# fob.net
KiCad netlist of a schematic drawn in EAGLE
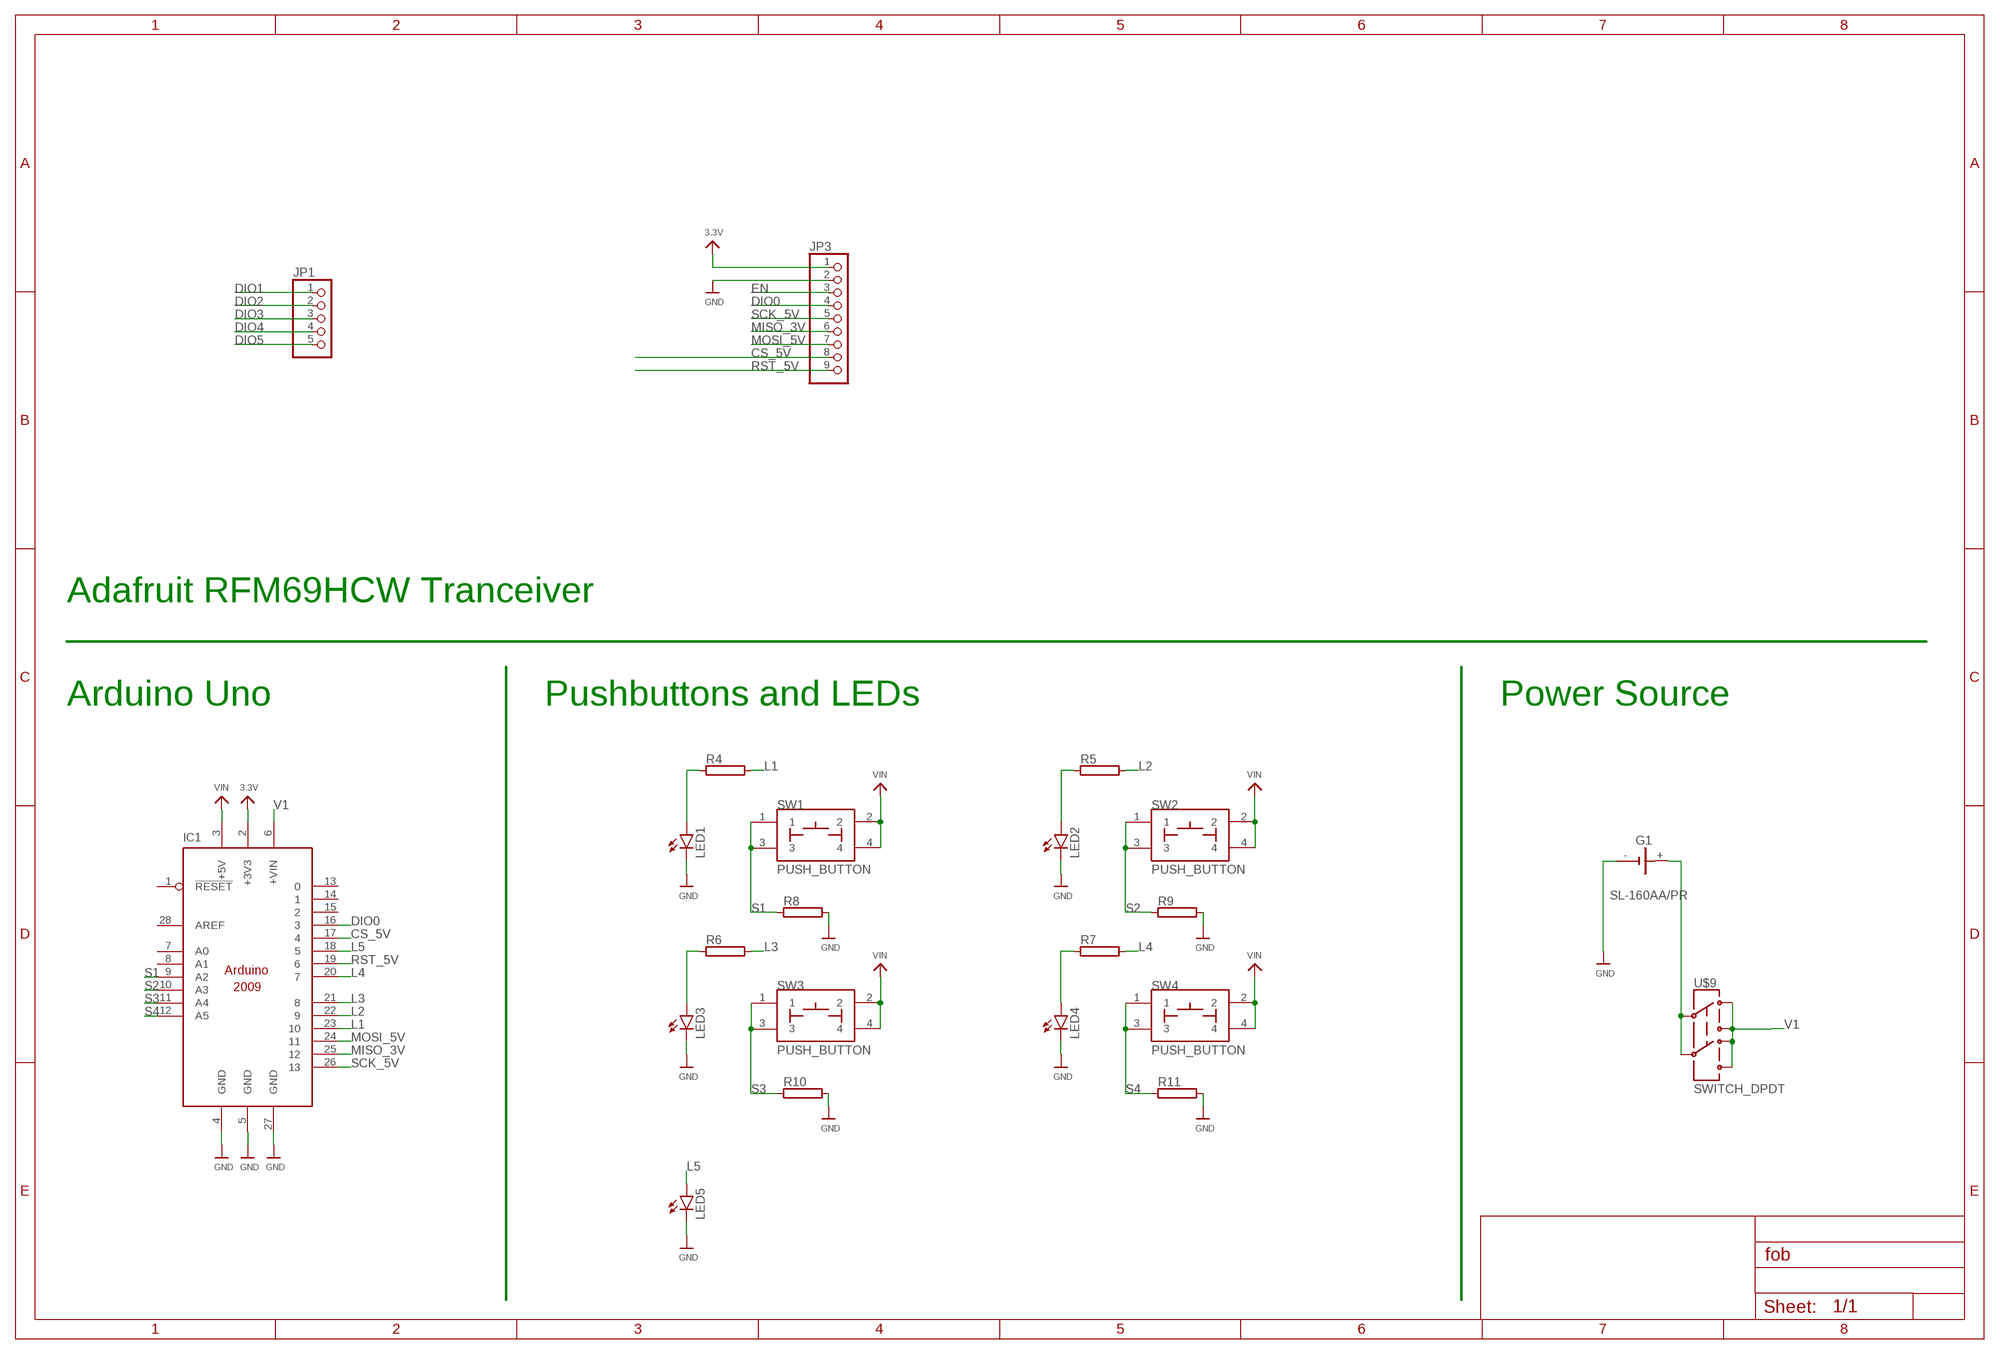
[diagram p0: schematic, sheet 1]

(export (version "E")
  (design (tool "Eeschema 10.0.6"))
  (components
    (comp (ref "G1")
      (value "SL-160AA/PR")
      (footprint "eagle-import:SL-160AA_PR")
      (libsource (lib "eagle-import") (part "SL-160AA/PR"))
    )
    (comp (ref "IC1")
      (value "ARDUINO2009_10")
      (footprint "eagle-import:ARDUINO2009")
      (libsource (lib "eagle-import") (part "ARDUINO2009_10"))
    )
    (comp (ref "JP1")
      (value "HEADER-1X570MIL")
      (footprint "eagle-import:1X05_ROUND_70")
      (libsource (lib "eagle-import") (part "HEADER-1X570MIL"))
    )
    (comp (ref "JP3")
      (value "HEADER-1X970MIL")
      (footprint "eagle-import:1X09_ROUND_70")
      (libsource (lib "eagle-import") (part "HEADER-1X970MIL"))
    )
    (comp (ref "LED1")
      (value "LED5MM")
      (footprint "eagle-import:LED5MM")
      (libsource (lib "eagle-import") (part "LED5MM"))
    )
    (comp (ref "LED2")
      (value "LED5MM")
      (footprint "eagle-import:LED5MM")
      (libsource (lib "eagle-import") (part "LED5MM"))
    )
    (comp (ref "LED3")
      (value "LED5MM")
      (footprint "eagle-import:LED5MM")
      (libsource (lib "eagle-import") (part "LED5MM"))
    )
    (comp (ref "LED4")
      (value "LED5MM")
      (footprint "eagle-import:LED5MM")
      (libsource (lib "eagle-import") (part "LED5MM"))
    )
    (comp (ref "LED5")
      (value "LED5MM")
      (footprint "eagle-import:LED5MM")
      (libsource (lib "eagle-import") (part "LED5MM"))
    )
    (comp (ref "R4")
      (value "RAC01")
      (footprint "eagle-import:AC01")
      (libsource (lib "eagle-import") (part "RAC01"))
    )
    (comp (ref "R5")
      (value "RAC01")
      (footprint "eagle-import:AC01")
      (libsource (lib "eagle-import") (part "RAC01"))
    )
    (comp (ref "R6")
      (value "RAC01")
      (footprint "eagle-import:AC01")
      (libsource (lib "eagle-import") (part "RAC01"))
    )
    (comp (ref "R7")
      (value "RAC01")
      (footprint "eagle-import:AC01")
      (libsource (lib "eagle-import") (part "RAC01"))
    )
    (comp (ref "R8")
      (value "RAC01")
      (footprint "eagle-import:AC01")
      (libsource (lib "eagle-import") (part "RAC01"))
    )
    (comp (ref "R9")
      (value "RAC01")
      (footprint "eagle-import:AC01")
      (libsource (lib "eagle-import") (part "RAC01"))
    )
    (comp (ref "R10")
      (value "RAC01")
      (footprint "eagle-import:AC01")
      (libsource (lib "eagle-import") (part "RAC01"))
    )
    (comp (ref "R11")
      (value "RAC01")
      (footprint "eagle-import:AC01")
      (libsource (lib "eagle-import") (part "RAC01"))
    )
    (comp (ref "SW1")
      (value "PUSH_BUTTON")
      (footprint "eagle-import:BUTTON_12.5MM")
      (libsource (lib "eagle-import") (part "PUSH_BUTTON"))
    )
    (comp (ref "SW2")
      (value "PUSH_BUTTON")
      (footprint "eagle-import:BUTTON_12.5MM")
      (libsource (lib "eagle-import") (part "PUSH_BUTTON"))
    )
    (comp (ref "SW3")
      (value "PUSH_BUTTON")
      (footprint "eagle-import:BUTTON_12.5MM")
      (libsource (lib "eagle-import") (part "PUSH_BUTTON"))
    )
    (comp (ref "SW4")
      (value "PUSH_BUTTON")
      (footprint "eagle-import:BUTTON_12.5MM")
      (libsource (lib "eagle-import") (part "PUSH_BUTTON"))
    )
    (comp (ref "U$9")
      (value "SWITCH_DPDT")
      (footprint "eagle-import:JS_DPDT_TH")
      (libsource (lib "eagle-import") (part "SWITCH_DPDT"))
    )
  )
  (nets
    (net (code "1") (name "/CS_5V") (class "Default")
      (node (ref "IC1") (pin "17") (pinfunction "4_17") (pintype "bidirectional"))
      (node (ref "JP3") (pin "8") (pinfunction "8_8") (pintype "passive"))
    )
    (net (code "2") (name "/DIO0") (class "Default")
      (node (ref "IC1") (pin "16") (pinfunction "3_16") (pintype "bidirectional"))
      (node (ref "JP3") (pin "4") (pinfunction "4_4") (pintype "passive"))
    )
    (net (code "3") (name "/DIO1") (class "Default")
      (node (ref "JP1") (pin "1") (pinfunction "1_1") (pintype "passive"))
    )
    (net (code "4") (name "/DIO2") (class "Default")
      (node (ref "JP1") (pin "2") (pinfunction "2_2") (pintype "passive"))
    )
    (net (code "5") (name "/DIO3") (class "Default")
      (node (ref "JP1") (pin "3") (pinfunction "3_3") (pintype "passive"))
    )
    (net (code "6") (name "/DIO4") (class "Default")
      (node (ref "JP1") (pin "4") (pinfunction "4_4") (pintype "passive"))
    )
    (net (code "7") (name "/DIO5") (class "Default")
      (node (ref "JP1") (pin "5") (pinfunction "5_5") (pintype "passive"))
    )
    (net (code "8") (name "/EN") (class "Default")
      (node (ref "JP3") (pin "3") (pinfunction "3_3") (pintype "passive"))
    )
    (net (code "9") (name "/L1") (class "Default")
      (node (ref "IC1") (pin "23") (pinfunction "10_23") (pintype "bidirectional"))
      (node (ref "R4") (pin "2") (pinfunction "2_2") (pintype "passive"))
    )
    (net (code "10") (name "/L2") (class "Default")
      (node (ref "IC1") (pin "22") (pinfunction "9_22") (pintype "bidirectional"))
      (node (ref "R5") (pin "2") (pinfunction "2_2") (pintype "passive"))
    )
    (net (code "11") (name "/L3") (class "Default")
      (node (ref "IC1") (pin "21") (pinfunction "8_21") (pintype "bidirectional"))
      (node (ref "R6") (pin "2") (pinfunction "2_2") (pintype "passive"))
    )
    (net (code "12") (name "/L4") (class "Default")
      (node (ref "IC1") (pin "20") (pinfunction "7_20") (pintype "bidirectional"))
      (node (ref "R7") (pin "2") (pinfunction "2_2") (pintype "passive"))
    )
    (net (code "13") (name "/L5") (class "Default")
      (node (ref "IC1") (pin "18") (pinfunction "5_18") (pintype "bidirectional"))
      (node (ref "LED5") (pin "A") (pinfunction "A_A") (pintype "passive"))
    )
    (net (code "14") (name "/MISO_3V") (class "Default")
      (node (ref "IC1") (pin "25") (pinfunction "12_25") (pintype "bidirectional"))
      (node (ref "JP3") (pin "6") (pinfunction "6_6") (pintype "passive"))
    )
    (net (code "15") (name "/MOSI_5V") (class "Default")
      (node (ref "IC1") (pin "24") (pinfunction "11_24") (pintype "bidirectional"))
      (node (ref "JP3") (pin "7") (pinfunction "7_7") (pintype "passive"))
    )
    (net (code "17") (name "/RST_5V") (class "Default")
      (node (ref "IC1") (pin "19") (pinfunction "6_19") (pintype "bidirectional"))
      (node (ref "JP3") (pin "9") (pinfunction "9_9") (pintype "passive"))
    )
    (net (code "18") (name "/S1") (class "Default")
      (node (ref "IC1") (pin "9") (pinfunction "A2_9") (pintype "bidirectional"))
      (node (ref "R8") (pin "1") (pinfunction "1_1") (pintype "passive"))
      (node (ref "SW1") (pin "1") (pinfunction "1_1") (pintype "bidirectional"))
      (node (ref "SW1") (pin "3") (pinfunction "3_3") (pintype "bidirectional"))
    )
    (net (code "19") (name "/S2") (class "Default")
      (node (ref "IC1") (pin "10") (pinfunction "A3_10") (pintype "bidirectional"))
      (node (ref "R9") (pin "1") (pinfunction "1_1") (pintype "passive"))
      (node (ref "SW2") (pin "1") (pinfunction "1_1") (pintype "bidirectional"))
      (node (ref "SW2") (pin "3") (pinfunction "3_3") (pintype "bidirectional"))
    )
    (net (code "20") (name "/S3") (class "Default")
      (node (ref "IC1") (pin "11") (pinfunction "A4_11") (pintype "bidirectional"))
      (node (ref "R10") (pin "1") (pinfunction "1_1") (pintype "passive"))
      (node (ref "SW3") (pin "1") (pinfunction "1_1") (pintype "bidirectional"))
      (node (ref "SW3") (pin "3") (pinfunction "3_3") (pintype "bidirectional"))
    )
    (net (code "21") (name "/S4") (class "Default")
      (node (ref "IC1") (pin "12") (pinfunction "A5_12") (pintype "bidirectional"))
      (node (ref "R11") (pin "1") (pinfunction "1_1") (pintype "passive"))
      (node (ref "SW4") (pin "1") (pinfunction "1_1") (pintype "bidirectional"))
      (node (ref "SW4") (pin "3") (pinfunction "3_3") (pintype "bidirectional"))
    )
    (net (code "22") (name "/SCK_5V") (class "Default")
      (node (ref "IC1") (pin "26") (pinfunction "13_26") (pintype "bidirectional"))
      (node (ref "JP3") (pin "5") (pinfunction "5_5") (pintype "passive"))
    )
    (net (code "23") (name "/V1") (class "Default")
      (node (ref "IC1") (pin "6") (pinfunction "+VIN_6") (pintype "bidirectional"))
      (node (ref "U$9") (pin "1") (pinfunction "1_1") (pintype "bidirectional"))
      (node (ref "U$9") (pin "3") (pinfunction "3_3") (pintype "bidirectional"))
      (node (ref "U$9") (pin "4") (pinfunction "4_4") (pintype "bidirectional"))
      (node (ref "U$9") (pin "6") (pinfunction "6_6") (pintype "bidirectional"))
    )
    (net (code "24") (name "3.3V") (class "Default")
      (node (ref "IC1") (pin "2") (pinfunction "+3V3_2") (pintype "power_in"))
      (node (ref "JP3") (pin "1") (pinfunction "1_1") (pintype "passive"))
    )
    (net (code "25") (name "GND") (class "Default")
      (node (ref "G1") (pin "-") (pinfunction "-_-") (pintype "passive"))
      (node (ref "IC1") (pin "27") (pinfunction "GND_27") (pintype "power_in"))
      (node (ref "IC1") (pin "4") (pinfunction "GND_4") (pintype "power_in"))
      (node (ref "IC1") (pin "5") (pinfunction "GND_5") (pintype "power_in"))
      (node (ref "JP3") (pin "2") (pinfunction "2_2") (pintype "passive"))
      (node (ref "LED1") (pin "K") (pinfunction "C_K") (pintype "passive"))
      (node (ref "LED2") (pin "K") (pinfunction "C_K") (pintype "passive"))
      (node (ref "LED3") (pin "K") (pinfunction "C_K") (pintype "passive"))
      (node (ref "LED4") (pin "K") (pinfunction "C_K") (pintype "passive"))
      (node (ref "LED5") (pin "K") (pinfunction "C_K") (pintype "passive"))
      (node (ref "R10") (pin "2") (pinfunction "2_2") (pintype "passive"))
      (node (ref "R11") (pin "2") (pinfunction "2_2") (pintype "passive"))
      (node (ref "R8") (pin "2") (pinfunction "2_2") (pintype "passive"))
      (node (ref "R9") (pin "2") (pinfunction "2_2") (pintype "passive"))
    )
    (net (code "26") (name "Net-(G1-Pad+)") (class "Default")
      (node (ref "G1") (pin "+") (pinfunction "+_+") (pintype "passive"))
      (node (ref "U$9") (pin "2") (pinfunction "2_2") (pintype "bidirectional"))
      (node (ref "U$9") (pin "5") (pinfunction "5_5") (pintype "bidirectional"))
    )
    (net (code "27") (name "Net-(LED1-PadA)") (class "Default")
      (node (ref "LED1") (pin "A") (pinfunction "A_A") (pintype "passive"))
      (node (ref "R4") (pin "1") (pinfunction "1_1") (pintype "passive"))
    )
    (net (code "28") (name "Net-(LED2-PadA)") (class "Default")
      (node (ref "LED2") (pin "A") (pinfunction "A_A") (pintype "passive"))
      (node (ref "R5") (pin "1") (pinfunction "1_1") (pintype "passive"))
    )
    (net (code "29") (name "Net-(LED3-PadA)") (class "Default")
      (node (ref "LED3") (pin "A") (pinfunction "A_A") (pintype "passive"))
      (node (ref "R6") (pin "1") (pinfunction "1_1") (pintype "passive"))
    )
    (net (code "30") (name "Net-(LED4-PadA)") (class "Default")
      (node (ref "LED4") (pin "A") (pinfunction "A_A") (pintype "passive"))
      (node (ref "R7") (pin "1") (pinfunction "1_1") (pintype "passive"))
    )
    (net (code "31") (name "VIN") (class "Default")
      (node (ref "IC1") (pin "3") (pinfunction "+5V_3") (pintype "power_in"))
      (node (ref "SW1") (pin "2") (pinfunction "2_2") (pintype "bidirectional"))
      (node (ref "SW1") (pin "4") (pinfunction "4_4") (pintype "bidirectional"))
      (node (ref "SW2") (pin "2") (pinfunction "2_2") (pintype "bidirectional"))
      (node (ref "SW2") (pin "4") (pinfunction "4_4") (pintype "bidirectional"))
      (node (ref "SW3") (pin "2") (pinfunction "2_2") (pintype "bidirectional"))
      (node (ref "SW3") (pin "4") (pinfunction "4_4") (pintype "bidirectional"))
      (node (ref "SW4") (pin "2") (pinfunction "2_2") (pintype "bidirectional"))
      (node (ref "SW4") (pin "4") (pinfunction "4_4") (pintype "bidirectional"))
    )
    (net (code "32") (name "unconnected-(IC1-0-Pad13)") (class "Default")
      (node (ref "IC1") (pin "13") (pinfunction "0_13") (pintype "bidirectional"))
    )
    (net (code "33") (name "unconnected-(IC1-1-Pad14)") (class "Default")
      (node (ref "IC1") (pin "14") (pinfunction "1_14") (pintype "bidirectional"))
    )
    (net (code "34") (name "unconnected-(IC1-2-Pad15)") (class "Default")
      (node (ref "IC1") (pin "15") (pinfunction "2_15") (pintype "bidirectional"))
    )
    (net (code "35") (name "unconnected-(IC1-A0-Pad7)") (class "Default")
      (node (ref "IC1") (pin "7") (pinfunction "A0_7") (pintype "bidirectional"))
    )
    (net (code "36") (name "unconnected-(IC1-A1-Pad8)") (class "Default")
      (node (ref "IC1") (pin "8") (pinfunction "A1_8") (pintype "bidirectional"))
    )
    (net (code "37") (name "unconnected-(IC1-AREF-Pad28)") (class "Default")
      (node (ref "IC1") (pin "28") (pinfunction "AREF_28") (pintype "bidirectional"))
    )
    (net (code "38") (name "unconnected-(IC1-~{RESET}-Pad1)") (class "Default")
      (node (ref "IC1") (pin "1") (pinfunction "~{RESET}_1") (pintype "bidirectional"))
    )
  )
)
